# 28Pins_Schematic.net
KiCad netlist of a schematic drawn in Altium Designer
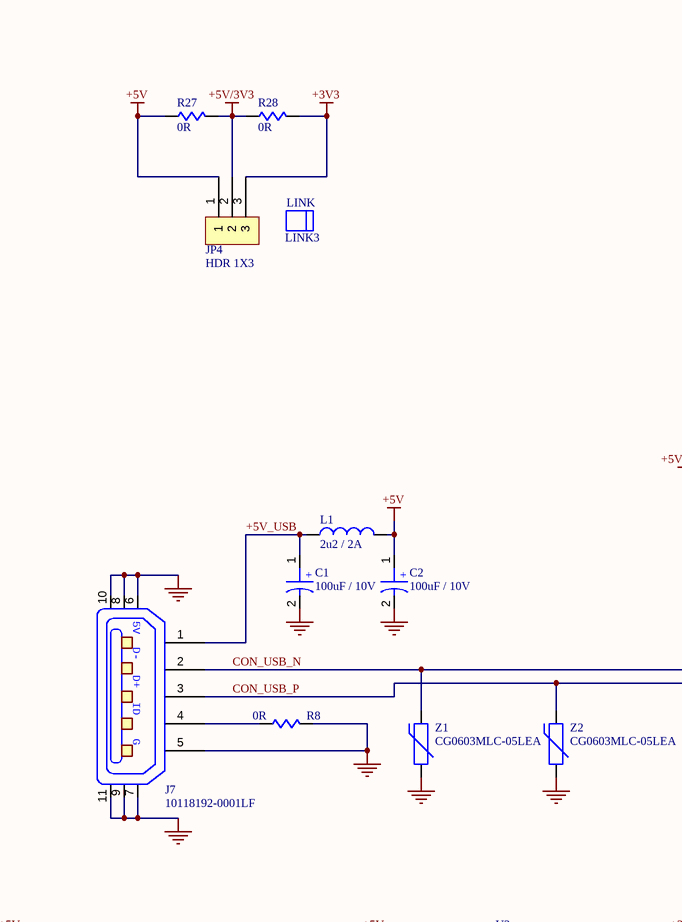
[diagram p0: 28Pins_Schematic.SchDoc, top left]
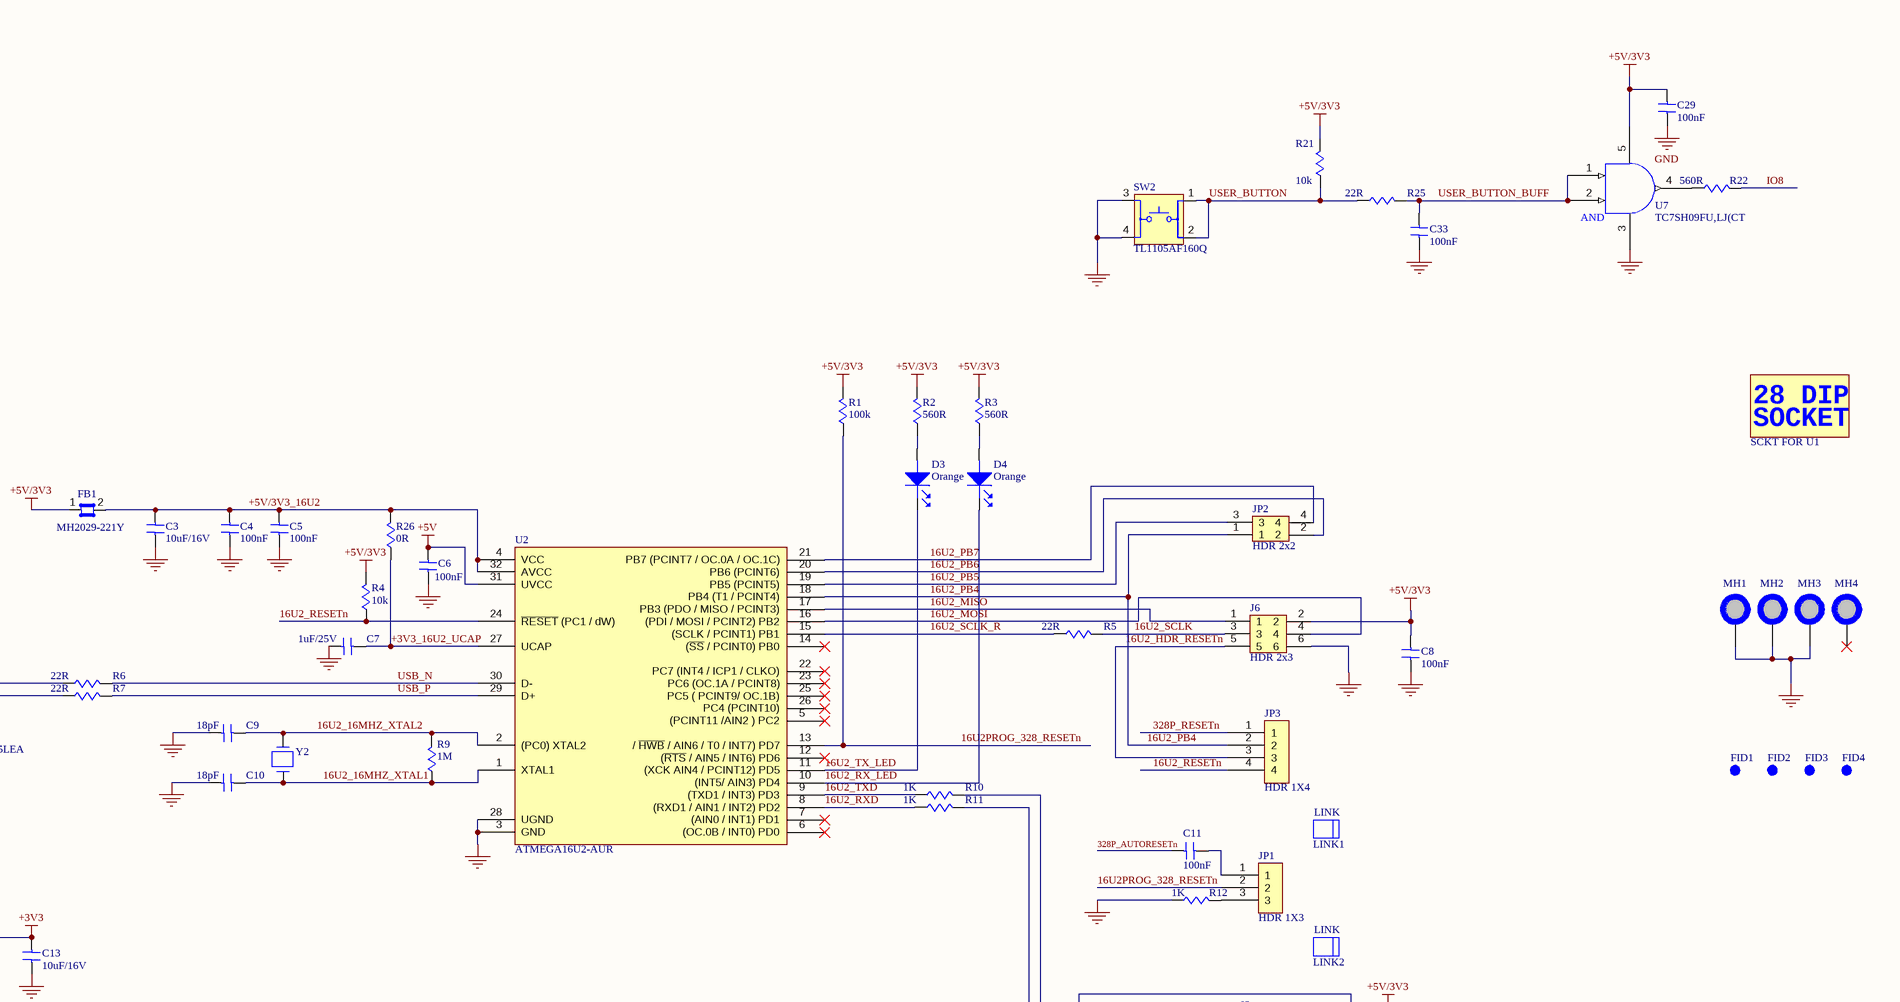
[diagram p1: 28Pins_Schematic.SchDoc, top right]
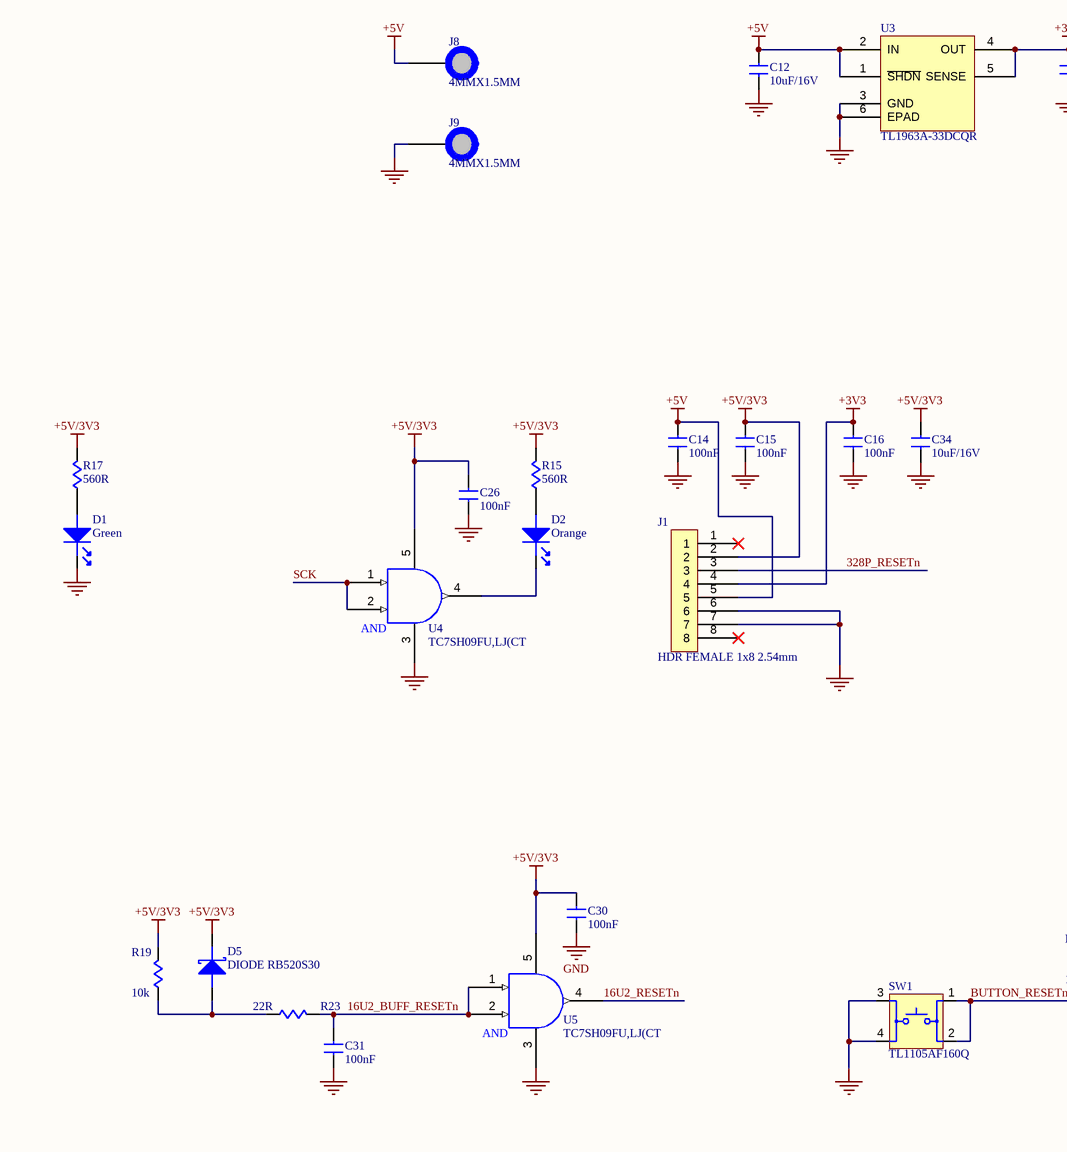
[diagram p2: 28Pins_Schematic.SchDoc, bottom left]
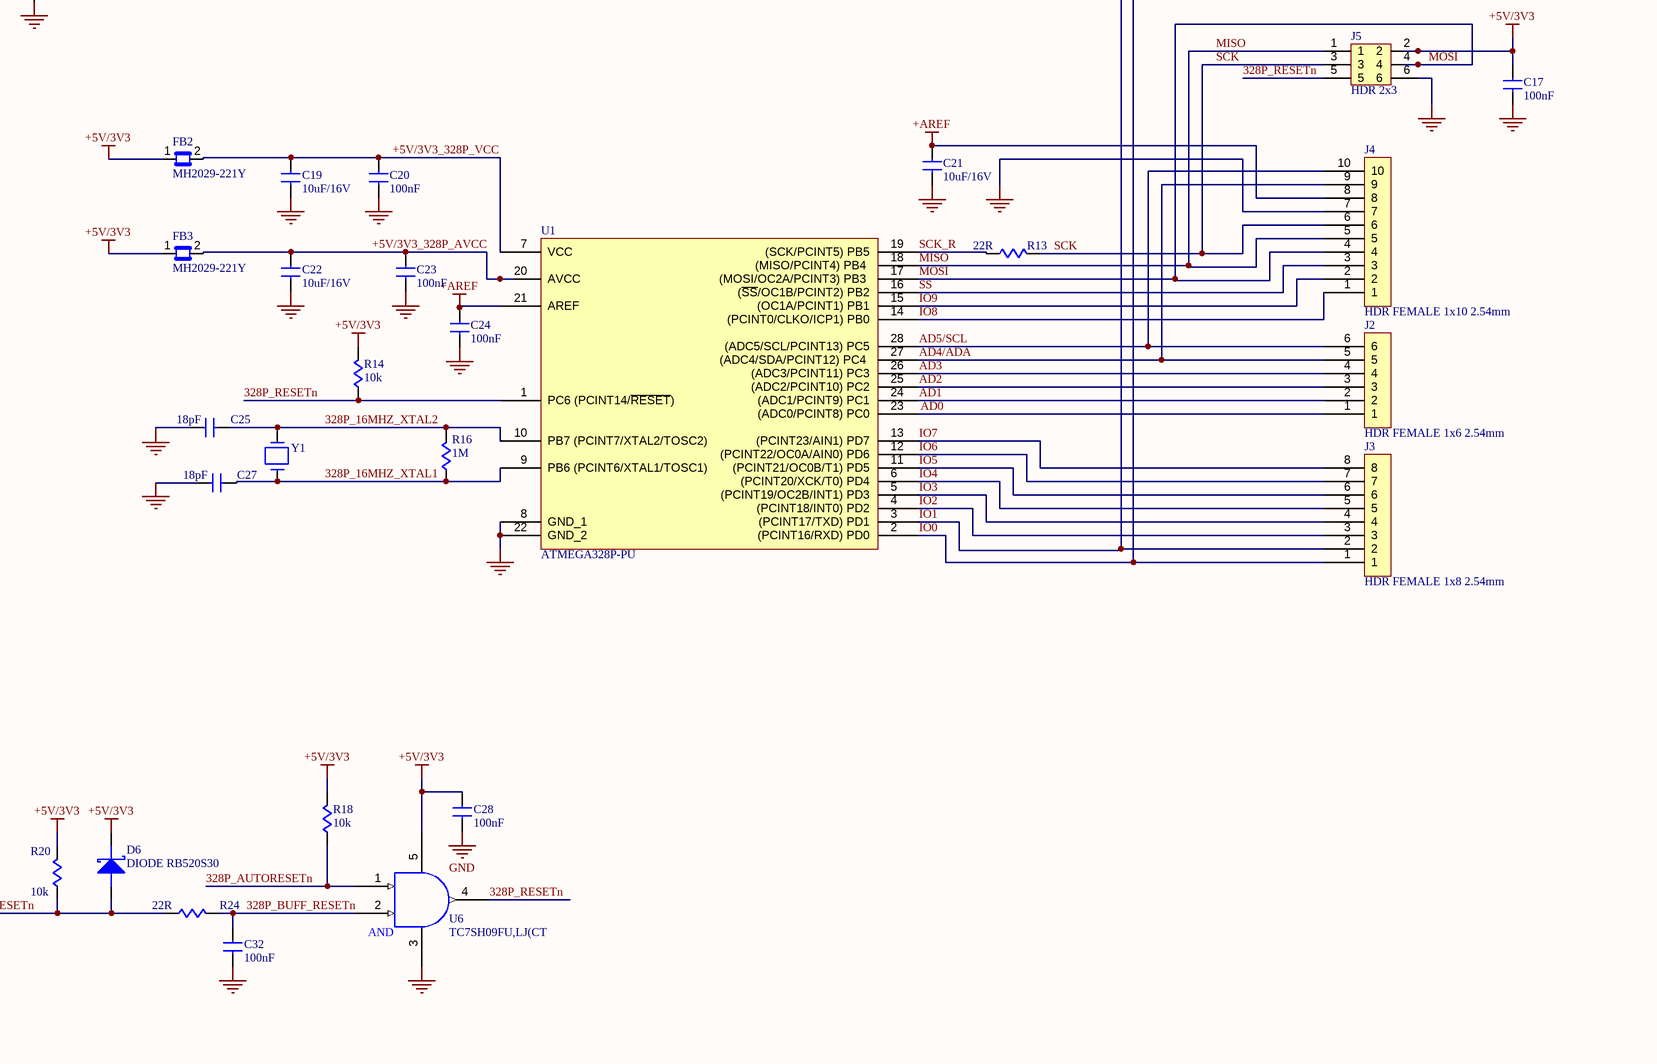
[diagram p3: 28Pins_Schematic.SchDoc, bottom right]

(export (version "E")
  (design (tool "Eeschema 10.0.6"))
  (components
    (comp (ref "C1")
      (value "100uF / 10V")
      (footprint "C_ALU_C_SIZE")
      (description "CAP ALUM 100UF 20% 10V SMD")
      (fields
        (field (name "MANUFACTURER") "Panasonic")
        (field (name "MANUFACTURER PART NUMBER") "EEE-1AA101WAR")
      )
      (libsource (lib "28Pins_Project") (part "EEE-1AA101WAR"))
    )
    (comp (ref "C2")
      (value "100uF / 10V")
      (footprint "C_ALU_C_SIZE")
      (description "CAP ALUM 100UF 20% 10V SMD")
      (fields
        (field (name "MANUFACTURER") "Panasonic")
        (field (name "MANUFACTURER PART NUMBER") "EEE-1AA101WAR")
      )
      (libsource (lib "28Pins_Project") (part "EEE-1AA101WAR"))
    )
    (comp (ref "C3")
      (value "10uF/16V")
      (footprint "C0805")
      (description "CAP CER 10UF 16V X5R 0805")
      (fields
        (field (name "MANUFACTURER") "Murata")
        (field (name "MANUFACTURER PART NUMBER") "GRM21BR61C106KE15L")
      )
      (libsource (lib "28Pins_Project") (part "GRM21BR61C106KE15L"))
    )
    (comp (ref "C4")
      (value "100nF")
      (footprint "C0805")
      (fields
        (field (name "MANUFACTURER") "Kyocera AVX")
        (field (name "MANUFACTURER PART NUMBER") "08055C104K4T4A")
        (field (name "TOLERANCE") "10%")
      )
      (libsource (lib "28Pins_Project") (part "08055C104K4T4A"))
    )
    (comp (ref "C5")
      (value "100nF")
      (footprint "C0805")
      (fields
        (field (name "MANUFACTURER") "Kyocera AVX")
        (field (name "MANUFACTURER PART NUMBER") "08055C104K4T4A")
        (field (name "TOLERANCE") "10%")
      )
      (libsource (lib "28Pins_Project") (part "08055C104K4T4A"))
    )
    (comp (ref "C6")
      (value "100nF")
      (footprint "C0805")
      (fields
        (field (name "MANUFACTURER") "Kyocera AVX")
        (field (name "MANUFACTURER PART NUMBER") "08055C104K4T4A")
        (field (name "TOLERANCE") "10%")
      )
      (libsource (lib "28Pins_Project") (part "08055C104K4T4A"))
    )
    (comp (ref "C7")
      (value "1uF/25V")
      (footprint "C0805")
      (fields
        (field (name "MANUFACTURER") "TDK")
        (field (name "MANUFACTURER PART NUMBER") "C2012X5R1E105K125AA")
        (field (name "TOLERANCE") "10%")
      )
      (libsource (lib "28Pins_Project") (part "C2012X5R1E105K125AA"))
    )
    (comp (ref "C8")
      (value "100nF")
      (footprint "C0805")
      (fields
        (field (name "MANUFACTURER") "Kyocera AVX")
        (field (name "MANUFACTURER PART NUMBER") "08055C104K4T4A")
        (field (name "TOLERANCE") "10%")
      )
      (libsource (lib "28Pins_Project") (part "08055C104K4T4A"))
    )
    (comp (ref "C9")
      (value "18pF")
      (footprint "C0805")
      (description "CAP CER 18pF")
      (fields
        (field (name "MANUFACTURER") "Murata")
        (field (name "MANUFACTURER PART NUMBER") "GJM1551C1HR56BB01D")
      )
      (libsource (lib "28Pins_Project") (part "GJM1551C1HR56BB01D"))
    )
    (comp (ref "C10")
      (value "18pF")
      (footprint "C0805")
      (description "CAP CER 18pF")
      (fields
        (field (name "MANUFACTURER") "Murata")
        (field (name "MANUFACTURER PART NUMBER") "GJM1551C1HR56BB01D")
      )
      (libsource (lib "28Pins_Project") (part "GJM1551C1HR56BB01D"))
    )
    (comp (ref "C11")
      (value "100nF")
      (footprint "C0805")
      (fields
        (field (name "MANUFACTURER") "Kyocera AVX")
        (field (name "MANUFACTURER PART NUMBER") "08055C104K4T4A")
        (field (name "TOLERANCE") "10%")
      )
      (libsource (lib "28Pins_Project") (part "08055C104K4T4A"))
    )
    (comp (ref "C12")
      (value "10uF/16V")
      (footprint "C0805")
      (description "CAP CER 10UF 16V X5R 0805")
      (fields
        (field (name "MANUFACTURER") "Murata")
        (field (name "MANUFACTURER PART NUMBER") "GRM21BR61C106KE15L")
      )
      (libsource (lib "28Pins_Project") (part "GRM21BR61C106KE15L"))
    )
    (comp (ref "C13")
      (value "10uF/16V")
      (footprint "C0805")
      (description "CAP CER 10UF 16V X5R 0805")
      (fields
        (field (name "MANUFACTURER") "Murata")
        (field (name "MANUFACTURER PART NUMBER") "GRM21BR61C106KE15L")
      )
      (libsource (lib "28Pins_Project") (part "GRM21BR61C106KE15L"))
    )
    (comp (ref "C14")
      (value "100nF")
      (footprint "C0805")
      (fields
        (field (name "MANUFACTURER") "Kyocera AVX")
        (field (name "MANUFACTURER PART NUMBER") "08055C104K4T4A")
        (field (name "TOLERANCE") "10%")
      )
      (libsource (lib "28Pins_Project") (part "08055C104K4T4A"))
    )
    (comp (ref "C15")
      (value "100nF")
      (footprint "C0805")
      (fields
        (field (name "MANUFACTURER") "Kyocera AVX")
        (field (name "MANUFACTURER PART NUMBER") "08055C104K4T4A")
        (field (name "TOLERANCE") "10%")
      )
      (libsource (lib "28Pins_Project") (part "08055C104K4T4A"))
    )
    (comp (ref "C16")
      (value "100nF")
      (footprint "C0805")
      (fields
        (field (name "MANUFACTURER") "Kyocera AVX")
        (field (name "MANUFACTURER PART NUMBER") "08055C104K4T4A")
        (field (name "TOLERANCE") "10%")
      )
      (libsource (lib "28Pins_Project") (part "08055C104K4T4A"))
    )
    (comp (ref "C17")
      (value "100nF")
      (footprint "C0805")
      (fields
        (field (name "MANUFACTURER") "Kyocera AVX")
        (field (name "MANUFACTURER PART NUMBER") "08055C104K4T4A")
        (field (name "TOLERANCE") "10%")
      )
      (libsource (lib "28Pins_Project") (part "08055C104K4T4A"))
    )
    (comp (ref "C19")
      (value "10uF/16V")
      (footprint "C0805")
      (description "CAP CER 10UF 16V X5R 0805")
      (fields
        (field (name "MANUFACTURER") "Murata")
        (field (name "MANUFACTURER PART NUMBER") "GRM21BR61C106KE15L")
      )
      (libsource (lib "28Pins_Project") (part "GRM21BR61C106KE15L"))
    )
    (comp (ref "C20")
      (value "100nF")
      (footprint "C0805")
      (fields
        (field (name "MANUFACTURER") "Kyocera AVX")
        (field (name "MANUFACTURER PART NUMBER") "08055C104K4T4A")
        (field (name "TOLERANCE") "10%")
      )
      (libsource (lib "28Pins_Project") (part "08055C104K4T4A"))
    )
    (comp (ref "C21")
      (value "10uF/16V")
      (footprint "C0805")
      (description "CAP CER 10UF 16V X5R 0805")
      (fields
        (field (name "MANUFACTURER") "Murata")
        (field (name "MANUFACTURER PART NUMBER") "GRM21BR61C106KE15L")
      )
      (libsource (lib "28Pins_Project") (part "GRM21BR61C106KE15L"))
    )
    (comp (ref "C22")
      (value "10uF/16V")
      (footprint "C0805")
      (description "CAP CER 10UF 16V X5R 0805")
      (fields
        (field (name "MANUFACTURER") "Murata")
        (field (name "MANUFACTURER PART NUMBER") "GRM21BR61C106KE15L")
      )
      (libsource (lib "28Pins_Project") (part "GRM21BR61C106KE15L"))
    )
    (comp (ref "C23")
      (value "100nF")
      (footprint "C0805")
      (fields
        (field (name "MANUFACTURER") "Kyocera AVX")
        (field (name "MANUFACTURER PART NUMBER") "08055C104K4T4A")
        (field (name "TOLERANCE") "10%")
      )
      (libsource (lib "28Pins_Project") (part "08055C104K4T4A"))
    )
    (comp (ref "C24")
      (value "100nF")
      (footprint "C0805")
      (fields
        (field (name "MANUFACTURER") "Kyocera AVX")
        (field (name "MANUFACTURER PART NUMBER") "08055C104K4T4A")
        (field (name "TOLERANCE") "10%")
      )
      (libsource (lib "28Pins_Project") (part "08055C104K4T4A"))
    )
    (comp (ref "C25")
      (value "18pF")
      (footprint "C0805")
      (description "CAP CER 18pF")
      (fields
        (field (name "MANUFACTURER") "Murata")
        (field (name "MANUFACTURER PART NUMBER") "GJM1551C1HR56BB01D")
      )
      (libsource (lib "28Pins_Project") (part "GJM1551C1HR56BB01D"))
    )
    (comp (ref "C26")
      (value "100nF")
      (footprint "C0805")
      (fields
        (field (name "MANUFACTURER") "Kyocera AVX")
        (field (name "MANUFACTURER PART NUMBER") "08055C104K4T4A")
        (field (name "TOLERANCE") "10%")
      )
      (libsource (lib "28Pins_Project") (part "08055C104K4T4A"))
    )
    (comp (ref "C27")
      (value "18pF")
      (footprint "C0805")
      (description "CAP CER 18pF")
      (fields
        (field (name "MANUFACTURER") "Murata")
        (field (name "MANUFACTURER PART NUMBER") "GJM1551C1HR56BB01D")
      )
      (libsource (lib "28Pins_Project") (part "GJM1551C1HR56BB01D"))
    )
    (comp (ref "C28")
      (value "100nF")
      (footprint "C0805")
      (fields
        (field (name "MANUFACTURER") "Kyocera AVX")
        (field (name "MANUFACTURER PART NUMBER") "08055C104K4T4A")
        (field (name "TOLERANCE") "10%")
      )
      (libsource (lib "28Pins_Project") (part "08055C104K4T4A"))
    )
    (comp (ref "C29")
      (value "100nF")
      (footprint "C0805")
      (fields
        (field (name "MANUFACTURER") "Kyocera AVX")
        (field (name "MANUFACTURER PART NUMBER") "08055C104K4T4A")
        (field (name "TOLERANCE") "10%")
      )
      (libsource (lib "28Pins_Project") (part "08055C104K4T4A"))
    )
    (comp (ref "C30")
      (value "100nF")
      (footprint "C0805")
      (fields
        (field (name "MANUFACTURER") "Kyocera AVX")
        (field (name "MANUFACTURER PART NUMBER") "08055C104K4T4A")
        (field (name "TOLERANCE") "10%")
      )
      (libsource (lib "28Pins_Project") (part "08055C104K4T4A"))
    )
    (comp (ref "C31")
      (value "100nF")
      (footprint "C0805")
      (fields
        (field (name "MANUFACTURER") "Kyocera AVX")
        (field (name "MANUFACTURER PART NUMBER") "08055C104K4T4A")
        (field (name "TOLERANCE") "10%")
      )
      (libsource (lib "28Pins_Project") (part "08055C104K4T4A"))
    )
    (comp (ref "C32")
      (value "100nF")
      (footprint "C0805")
      (fields
        (field (name "MANUFACTURER") "Kyocera AVX")
        (field (name "MANUFACTURER PART NUMBER") "08055C104K4T4A")
        (field (name "TOLERANCE") "10%")
      )
      (libsource (lib "28Pins_Project") (part "08055C104K4T4A"))
    )
    (comp (ref "C33")
      (value "100nF")
      (footprint "C0805")
      (fields
        (field (name "MANUFACTURER") "Kyocera AVX")
        (field (name "MANUFACTURER PART NUMBER") "08055C104K4T4A")
        (field (name "TOLERANCE") "10%")
      )
      (libsource (lib "28Pins_Project") (part "08055C104K4T4A"))
    )
    (comp (ref "C34")
      (value "10uF/16V")
      (footprint "C0805")
      (description "CAP CER 10UF 16V X5R 0805")
      (fields
        (field (name "MANUFACTURER") "Murata")
        (field (name "MANUFACTURER PART NUMBER") "GRM21BR61C106KE15L")
      )
      (libsource (lib "28Pins_Project") (part "GRM21BR61C106KE15L"))
    )
    (comp (ref "D1")
      (value "Green")
      (footprint "LED_0603")
      (description "LED Uni-Color Green 572nm Automotive 2-Pin Chip 0603(1608Metric) T/R")
      (fields
        (field (name "MANUFACTURER") "Osram Opto")
        (field (name "MANUFACTURER PART NUMBER") "LGL29K-F2J1-24-Z")
      )
      (libsource (lib "28Pins_Project") (part "LGL29K-F2J1-24-Z"))
    )
    (comp (ref "D2")
      (value "Orange")
      (footprint "LED_0603")
      (description "OSRAM - LO L29K-H2K1-24-Z - SMARTLED 0603 ORANGE 55AC2374")
      (fields
        (field (name "MANUFACTURER") "Osram Opto")
        (field (name "MANUFACTURER PART NUMBER") "LOL29K-H2K1-24-Z")
      )
      (libsource (lib "28Pins_Project") (part "LOL29K-H2K1-24-Z"))
    )
    (comp (ref "D3")
      (value "Orange")
      (footprint "LED_0603")
      (description "OSRAM - LO L29K-H2K1-24-Z - SMARTLED 0603 ORANGE 55AC2374")
      (fields
        (field (name "MANUFACTURER") "Osram Opto")
        (field (name "MANUFACTURER PART NUMBER") "LOL29K-H2K1-24-Z")
      )
      (libsource (lib "28Pins_Project") (part "LOL29K-H2K1-24-Z"))
    )
    (comp (ref "D4")
      (value "Orange")
      (footprint "LED_0603")
      (description "OSRAM - LO L29K-H2K1-24-Z - SMARTLED 0603 ORANGE 55AC2374")
      (fields
        (field (name "MANUFACTURER") "Osram Opto")
        (field (name "MANUFACTURER PART NUMBER") "LOL29K-H2K1-24-Z")
      )
      (libsource (lib "28Pins_Project") (part "LOL29K-H2K1-24-Z"))
    )
    (comp (ref "D5")
      (value "DIODE RB520S30")
      (footprint "SOD523")
      (description "DIODE, SCHOTTKY, 200mA, 30V, SOD-523F FAIRCHILD SEMICONDUCTOR RB520S30")
      (fields
        (field (name "MANUFACTURER") "ON Semiconductor / Fairchild")
        (field (name "MANUFACTURER PART NUMBER") "RB520S30")
      )
      (libsource (lib "28Pins_Project") (part "RB520S30"))
    )
    (comp (ref "D6")
      (value "DIODE RB520S30")
      (footprint "SOD523")
      (description "DIODE, SCHOTTKY, 200mA, 30V, SOD-523F FAIRCHILD SEMICONDUCTOR RB520S30")
      (fields
        (field (name "MANUFACTURER") "ON Semiconductor / Fairchild")
        (field (name "MANUFACTURER PART NUMBER") "RB520S30")
      )
      (libsource (lib "28Pins_Project") (part "RB520S30"))
    )
    (comp (ref "FB1")
      (value "MH2029-221Y")
      (footprint "FB0805")
      (description "BEAD FERRITE 220 OHM 2.0A 0805")
      (fields (field (name "MANUFACTURER") "Bourns") (field (name "TOLERANCE") "25%"))
      (libsource (lib "28Pins_Project") (part "MH2029-221Y"))
    )
    (comp (ref "FB2")
      (value "MH2029-221Y")
      (footprint "FB0805")
      (description "BEAD FERRITE 220 OHM 2.0A 0805")
      (fields (field (name "MANUFACTURER") "Bourns") (field (name "TOLERANCE") "25%"))
      (libsource (lib "28Pins_Project") (part "MH2029-221Y"))
    )
    (comp (ref "FB3")
      (value "MH2029-221Y")
      (footprint "FB0805")
      (description "BEAD FERRITE 220 OHM 2.0A 0805")
      (fields (field (name "MANUFACTURER") "Bourns") (field (name "TOLERANCE") "25%"))
      (libsource (lib "28Pins_Project") (part "MH2029-221Y"))
    )
    (comp (ref "FID1")
      (value "Fiducial 40mil Diameter 120mil solder mask")
      (footprint "FID_40X120D")
      (libsource (lib "28Pins_Project") (part "FID_1MMC"))
    )
    (comp (ref "FID2")
      (value "Fiducial 40mil Diameter 120mil solder mask")
      (footprint "FID_40X120D")
      (libsource (lib "28Pins_Project") (part "FID_1MMC"))
    )
    (comp (ref "FID3")
      (value "Fiducial 40mil Diameter 120mil solder mask")
      (footprint "FID_40X120D")
      (libsource (lib "28Pins_Project") (part "FID_1MMC"))
    )
    (comp (ref "FID4")
      (value "Fiducial 40mil Diameter 120mil solder mask")
      (footprint "FID_40X120D")
      (libsource (lib "28Pins_Project") (part "FID_1MMC"))
    )
    (comp (ref "J1")
      (value "HDR FEMALE 1x8 2.54mm")
      (footprint "HDR_FEMALE_1x8_2.54mm")
      (description "CONN HEADER 8POS 0.1\" PITCH")
      (fields (field (name "MANUFACTURER") "Harwin") (field (name "MANUFACTURER PART NUMBER") "M20-7820842"))
      (libsource (lib "28Pins_Project") (part "M20-7820842"))
    )
    (comp (ref "J2")
      (value "HDR FEMALE 1x6 2.54mm")
      (footprint "HDR_FEMALE_1x6_2.54mm - duplicate")
      (description "CONN HEADER 6POS 0.1\" PITCH")
      (fields (field (name "MANUFACTURER") "Harwin") (field (name "MANUFACTURER PART NUMBER") "M20-7820646"))
      (libsource (lib "28Pins_Project") (part "M20-7820646"))
    )
    (comp (ref "J3")
      (value "HDR FEMALE 1x8 2.54mm")
      (footprint "HDR_FEMALE_1x8_2.54mm")
      (description "CONN HEADER 8POS 0.1\" PITCH")
      (fields (field (name "MANUFACTURER") "Harwin") (field (name "MANUFACTURER PART NUMBER") "M20-7820842"))
      (libsource (lib "") (part "M20-7820842_1"))
    )
    (comp (ref "J4")
      (value "HDR FEMALE 1x10 2.54mm")
      (footprint "HDR_FEMALE_1x10_2.54mm")
      (description "CONN HEADER 10POS 0.1\" PITCH HARWIN - M20-7821046")
      (fields (field (name "MANUFACTURER") "Harwin") (field (name "MANUFACTURER PART NUMBER") "M20-7821046"))
      (libsource (lib "28Pins_Project") (part "M20-7821046"))
    )
    (comp (ref "J5")
      (value "HDR 2x3")
      (footprint "HDR2X3_2.54MM")
      (description "AMPHENOL FCI   68602-206HLF   BOARD TO BOARD, HEADER, 6 POSITION, 2ROW")
      (fields
        (field (name "MANUFACTURER") "Amphenol ICC / FCI")
        (field (name "MANUFACTURER PART NUMBER") "68602-206HLF")
      )
      (libsource (lib "28Pins_Project") (part "68602-206HLF"))
    )
    (comp (ref "J6")
      (value "HDR 2x3")
      (footprint "HDR2X3_2.54MM")
      (description "AMPHENOL FCI   68602-206HLF   BOARD TO BOARD, HEADER, 6 POSITION, 2ROW")
      (fields
        (field (name "MANUFACTURER") "Amphenol ICC / FCI")
        (field (name "MANUFACTURER PART NUMBER") "68602-206HLF")
      )
      (libsource (lib "28Pins_Project") (part "68602-206HLF"))
    )
    (comp (ref "J7")
      (value "10118192-0001LF")
      (footprint "10118192")
      (description "CONN USB MICRO B RECPT SMT R/A")
      (fields (field (name "MANUFACTURER") "Amphenol ICC / FCI"))
      (libsource (lib "28Pins_Project") (part "10118192-0001LF"))
    )
    (comp (ref "J8")
      (value "4MMX1.5MM")
      (footprint "PAD_WITH_HOLE_4MMX1.5MM")
      (description "Pad with a hole 4mm x 1.5mm")
      (libsource (lib "28Pins_Project") (part "PAD_WITH_HOLE"))
    )
    (comp (ref "J9")
      (value "4MMX1.5MM")
      (footprint "PAD_WITH_HOLE_4MMX1.5MM")
      (description "Pad with a hole 4mm x 1.5mm")
      (libsource (lib "28Pins_Project") (part "PAD_WITH_HOLE"))
    )
    (comp (ref "JP1")
      (value "HDR 1X3")
      (footprint "HDR1X3_2.54MM")
      (description "CONN HEADER 3POS 0.1\" PITCH AMPHENOL ICC - 68000-103HLF, FCI BergStik II 68000 Series")
      (fields
        (field (name "MANUFACTURER") "Amphenol ICC")
        (field (name "MANUFACTURER PART NUMBER") "68000-103HLF")
      )
      (libsource (lib "") (part "68000-103HLF_1"))
    )
    (comp (ref "JP2")
      (value "HDR 2x2")
      (footprint "HDR2X2_2.54MM")
      (fields
        (field (name "MANUFACTURER") "AMPHENOL ICC (FCI)")
        (field (name "MANUFACTURER PART NUMBER") "77313-124-04LF")
      )
      (libsource (lib "28Pins_Project") (part "77313-124-04LF"))
    )
    (comp (ref "JP3")
      (value "HDR 1X4")
      (footprint "HDR_1x4_2.54mm")
      (description "CONN HEADER 4 POS 2.54mm Solder ST Thru-Hole Bag")
      (fields (field (name "MANUFACTURER") "ICC") (field (name "MANUFACTURER PART NUMBER") "68001-204HLF"))
      (libsource (lib "28Pins_Project") (part "68001-204HLF"))
    )
    (comp (ref "JP4")
      (value "HDR 1X3")
      (footprint "HDR1X3_2.54MM")
      (description "CONN HEADER 3POS 0.1\" PITCH AMPHENOL ICC - 68000-103HLF, FCI BergStik II 68000 Series")
      (fields
        (field (name "MANUFACTURER") "Amphenol ICC")
        (field (name "MANUFACTURER PART NUMBER") "68000-103HLF")
      )
      (libsource (lib "28Pins_Project") (part "68000-103HLF"))
    )
    (comp (ref "L1")
      (value "2u2 / 2A")
      (footprint "C1210_IND")
      (description "INDUCTOR  L1210R2R2MDWIT KEMET")
      (fields
        (field (name "MANUFACTURER") "KEMET")
        (field (name "MANUFACTURER PART NUMBER") "L1210R2R2MDWIT")
      )
      (libsource (lib "28Pins_Project") (part "L1210R2R2MDWIT"))
    )
    (comp (ref "LINK1")
      (value "LINK")
      (description "CONN JUMPER SHORTING .100\" GOLD")
      (fields
        (field (name "MANUFACTURER") "Sullins")
        (field (name "MANUFACTURER PART NUMBER") "QPC02SXGN-RC")
      )
      (libsource (lib "28Pins_Project") (part "QPC02SXGN-RC"))
    )
    (comp (ref "LINK2")
      (value "LINK")
      (description "CONN JUMPER SHORTING .100\" GOLD")
      (fields
        (field (name "MANUFACTURER") "Sullins")
        (field (name "MANUFACTURER PART NUMBER") "QPC02SXGN-RC")
      )
      (libsource (lib "28Pins_Project") (part "QPC02SXGN-RC"))
    )
    (comp (ref "LINK3")
      (value "LINK")
      (description "CONN JUMPER SHORTING .100\" GOLD")
      (fields
        (field (name "MANUFACTURER") "Sullins")
        (field (name "MANUFACTURER PART NUMBER") "QPC02SXGN-RC")
      )
      (libsource (lib "28Pins_Project") (part "QPC02SXGN-RC"))
    )
    (comp (ref "MH1")
      (value "MH_7.4MMC_3.2MMD")
      (footprint "MH_7.4MMD_3.2MMD")
      (description "Mounting hole 7.4mm diameter, 3.2mm drill")
      (libsource (lib "28Pins_Project") (part "MH_7.4MMC_3.2"))
    )
    (comp (ref "MH2")
      (value "MH_7.4MMC_3.2MMD")
      (footprint "MH_7.4MMD_3.2MMD")
      (description "Mounting hole 7.4mm diameter, 3.2mm drill")
      (libsource (lib "28Pins_Project") (part "MH_7.4MMC_3.2"))
    )
    (comp (ref "MH3")
      (value "MH_7.4MMC_3.2MMD")
      (footprint "MH_7.4MMD_3.2MMD")
      (description "Mounting hole 7.4mm diameter, 3.2mm drill")
      (libsource (lib "28Pins_Project") (part "MH_7.4MMC_3.2"))
    )
    (comp (ref "MH4")
      (value "MH_7.4MMNC_3.2MMD")
      (footprint "MH_7.2MMD_4.2MMD_NON_COPPER_NPTH")
      (description "Hole 7.4mm diamter (non copper) 3.2 mm dril NPTH")
      (libsource (lib "28Pins_Project") (part "MH_7.4MMNC_3.2MMD"))
    )
    (comp (ref "R1")
      (value "100k")
      (footprint "R0805")
      (description "Res Thick Film 0805 100K Ohm 1% 1/8W ±100ppm/°C Molded SMD Paper T/R")
      (fields
        (field (name "MANUFACTURER") "Yageo")
        (field (name "MANUFACTURER PART NUMBER") "RC0805FR-07100KL")
      )
      (libsource (lib "28Pins_Project") (part "RC0805FR-07100KL"))
    )
    (comp (ref "R2")
      (value "560R")
      (footprint "R0805")
      (description "Surface Mount Thick Film Resistor, RC Series, 560 ohm, 125 mW, - 1%, 150 V, 0805 [2012 Metric]")
      (fields
        (field (name "MANUFACTURER") "Yageo")
        (field (name "MANUFACTURER PART NUMBER") "RC0805FR-07560RL")
      )
      (libsource (lib "28Pins_Project") (part "RC0805FR-07560RL"))
    )
    (comp (ref "R3")
      (value "560R")
      (footprint "R0805")
      (description "Surface Mount Thick Film Resistor, RC Series, 560 ohm, 125 mW, - 1%, 150 V, 0805 [2012 Metric]")
      (fields
        (field (name "MANUFACTURER") "Yageo")
        (field (name "MANUFACTURER PART NUMBER") "RC0805FR-07560RL")
      )
      (libsource (lib "28Pins_Project") (part "RC0805FR-07560RL"))
    )
    (comp (ref "R4")
      (value "10k")
      (footprint "R0805")
      (description "RES SMD 10K OHM 1% 1/8W 0805")
      (fields
        (field (name "MANUFACTURER") "Yageo")
        (field (name "MANUFACTURER PART NUMBER") "RC0805FR-0710KL")
      )
      (libsource (lib "28Pins_Project") (part "RC0805FR-0710KL"))
    )
    (comp (ref "R5")
      (value "22R")
      (footprint "R0805")
      (description "RES SMD 22 OHM 1% 1/8W 0805")
      (fields
        (field (name "MANUFACTURER") "Yageo")
        (field (name "MANUFACTURER PART NUMBER") "RC0805FR-0722RL")
      )
      (libsource (lib "28Pins_Project") (part "RC0805FR-0722RL"))
    )
    (comp (ref "R6")
      (value "22R")
      (footprint "R0805")
      (description "RES SMD 22 OHM 1% 1/8W 0805")
      (fields
        (field (name "MANUFACTURER") "Yageo")
        (field (name "MANUFACTURER PART NUMBER") "RC0805FR-0722RL")
      )
      (libsource (lib "28Pins_Project") (part "RC0805FR-0722RL"))
    )
    (comp (ref "R7")
      (value "22R")
      (footprint "R0805")
      (description "RES SMD 22 OHM 1% 1/8W 0805")
      (fields
        (field (name "MANUFACTURER") "Yageo")
        (field (name "MANUFACTURER PART NUMBER") "RC0805FR-0722RL")
      )
      (libsource (lib "28Pins_Project") (part "RC0805FR-0722RL"))
    )
    (comp (ref "R8")
      (value "0R")
      (footprint "R0805")
      (description "Res Anti-Sulfured Jumper Thick Film 0805 0 Ohm 1/8W Molded Paper T/R")
      (fields
        (field (name "MANUFACTURER") "Bourns")
        (field (name "MANUFACTURER PART NUMBER") "CR0805AJ/-000EAS")
      )
      (libsource (lib "28Pins_Project") (part "CR0805AJ/-000EAS"))
    )
    (comp (ref "R9")
      (value "1M")
      (footprint "R0805")
      (description "RES SMD 1M OHM 1% 1/8W 0805")
      (fields
        (field (name "MANUFACTURER") "Yageo")
        (field (name "MANUFACTURER PART NUMBER") "RC0805FR-071ML")
      )
      (libsource (lib "28Pins_Project") (part "RC0805FR-071ML"))
    )
    (comp (ref "R10")
      (value "1K")
      (footprint "R0805")
      (description "RES SMD 1K OHM 1% 1/8W 0805")
      (fields
        (field (name "MANUFACTURER") "Yageo")
        (field (name "MANUFACTURER PART NUMBER") "RC0805FR-071KL")
      )
      (libsource (lib "28Pins_Project") (part "RC0805FR-071KL"))
    )
    (comp (ref "R11")
      (value "1K")
      (footprint "R0805")
      (description "RES SMD 1K OHM 1% 1/8W 0805")
      (fields
        (field (name "MANUFACTURER") "Yageo")
        (field (name "MANUFACTURER PART NUMBER") "RC0805FR-071KL")
      )
      (libsource (lib "28Pins_Project") (part "RC0805FR-071KL"))
    )
    (comp (ref "R12")
      (value "1K")
      (footprint "R0805")
      (description "RES SMD 1K OHM 1% 1/8W 0805")
      (fields
        (field (name "MANUFACTURER") "Yageo")
        (field (name "MANUFACTURER PART NUMBER") "RC0805FR-071KL")
      )
      (libsource (lib "28Pins_Project") (part "RC0805FR-071KL"))
    )
    (comp (ref "R13")
      (value "22R")
      (footprint "R0805")
      (description "RES SMD 22 OHM 1% 1/8W 0805")
      (fields
        (field (name "MANUFACTURER") "Yageo")
        (field (name "MANUFACTURER PART NUMBER") "RC0805FR-0722RL")
      )
      (libsource (lib "28Pins_Project") (part "RC0805FR-0722RL"))
    )
    (comp (ref "R14")
      (value "10k")
      (footprint "R0805")
      (description "RES SMD 10K OHM 1% 1/8W 0805")
      (fields
        (field (name "MANUFACTURER") "Yageo")
        (field (name "MANUFACTURER PART NUMBER") "RC0805FR-0710KL")
      )
      (libsource (lib "28Pins_Project") (part "RC0805FR-0710KL"))
    )
    (comp (ref "R15")
      (value "560R")
      (footprint "R0805")
      (description "Surface Mount Thick Film Resistor, RC Series, 560 ohm, 125 mW, - 1%, 150 V, 0805 [2012 Metric]")
      (fields
        (field (name "MANUFACTURER") "Yageo")
        (field (name "MANUFACTURER PART NUMBER") "RC0805FR-07560RL")
      )
      (libsource (lib "28Pins_Project") (part "RC0805FR-07560RL"))
    )
    (comp (ref "R16")
      (value "1M")
      (footprint "R0805")
      (description "RES SMD 1M OHM 1% 1/8W 0805")
      (fields
        (field (name "MANUFACTURER") "Yageo")
        (field (name "MANUFACTURER PART NUMBER") "RC0805FR-071ML")
      )
      (libsource (lib "28Pins_Project") (part "RC0805FR-071ML"))
    )
    (comp (ref "R17")
      (value "560R")
      (footprint "R0805")
      (description "Surface Mount Thick Film Resistor, RC Series, 560 ohm, 125 mW, - 1%, 150 V, 0805 [2012 Metric]")
      (fields
        (field (name "MANUFACTURER") "Yageo")
        (field (name "MANUFACTURER PART NUMBER") "RC0805FR-07560RL")
      )
      (libsource (lib "28Pins_Project") (part "RC0805FR-07560RL"))
    )
    (comp (ref "R18")
      (value "10k")
      (footprint "R0805")
      (description "RES SMD 10K OHM 1% 1/8W 0805")
      (fields
        (field (name "MANUFACTURER") "Yageo")
        (field (name "MANUFACTURER PART NUMBER") "RC0805FR-0710KL")
      )
      (libsource (lib "28Pins_Project") (part "RC0805FR-0710KL"))
    )
    (comp (ref "R19")
      (value "10k")
      (footprint "R0805")
      (description "RES SMD 10K OHM 1% 1/8W 0805")
      (fields
        (field (name "MANUFACTURER") "Yageo")
        (field (name "MANUFACTURER PART NUMBER") "RC0805FR-0710KL")
      )
      (libsource (lib "28Pins_Project") (part "RC0805FR-0710KL"))
    )
    (comp (ref "R20")
      (value "10k")
      (footprint "R0805")
      (description "RES SMD 10K OHM 1% 1/8W 0805")
      (fields
        (field (name "MANUFACTURER") "Yageo")
        (field (name "MANUFACTURER PART NUMBER") "RC0805FR-0710KL")
      )
      (libsource (lib "28Pins_Project") (part "RC0805FR-0710KL"))
    )
    (comp (ref "R21")
      (value "10k")
      (footprint "R0805")
      (description "RES SMD 10K OHM 1% 1/8W 0805")
      (fields
        (field (name "MANUFACTURER") "Yageo")
        (field (name "MANUFACTURER PART NUMBER") "RC0805FR-0710KL")
      )
      (libsource (lib "28Pins_Project") (part "RC0805FR-0710KL"))
    )
    (comp (ref "R22")
      (value "560R")
      (footprint "R0805")
      (description "Surface Mount Thick Film Resistor, RC Series, 560 ohm, 125 mW, - 1%, 150 V, 0805 [2012 Metric]")
      (fields
        (field (name "MANUFACTURER") "Yageo")
        (field (name "MANUFACTURER PART NUMBER") "RC0805FR-07560RL")
      )
      (libsource (lib "28Pins_Project") (part "RC0805FR-07560RL"))
    )
    (comp (ref "R23")
      (value "22R")
      (footprint "R0805")
      (description "RES SMD 22 OHM 1% 1/8W 0805")
      (fields
        (field (name "MANUFACTURER") "Yageo")
        (field (name "MANUFACTURER PART NUMBER") "RC0805FR-0722RL")
      )
      (libsource (lib "28Pins_Project") (part "RC0805FR-0722RL"))
    )
    (comp (ref "R24")
      (value "22R")
      (footprint "R0805")
      (description "RES SMD 22 OHM 1% 1/8W 0805")
      (fields
        (field (name "MANUFACTURER") "Yageo")
        (field (name "MANUFACTURER PART NUMBER") "RC0805FR-0722RL")
      )
      (libsource (lib "28Pins_Project") (part "RC0805FR-0722RL"))
    )
    (comp (ref "R25")
      (value "22R")
      (footprint "R0805")
      (description "RES SMD 22 OHM 1% 1/8W 0805")
      (fields
        (field (name "MANUFACTURER") "Yageo")
        (field (name "MANUFACTURER PART NUMBER") "RC0805FR-0722RL")
      )
      (libsource (lib "28Pins_Project") (part "RC0805FR-0722RL"))
    )
    (comp (ref "R26")
      (value "0R")
      (footprint "R0805")
      (description "Res Anti-Sulfured Jumper Thick Film 0805 0 Ohm 1/8W Molded Paper T/R")
      (fields
        (field (name "MANUFACTURER") "Bourns")
        (field (name "MANUFACTURER PART NUMBER") "CR0805AJ/-000EAS")
      )
      (libsource (lib "28Pins_Project") (part "CR0805AJ/-000EAS"))
    )
    (comp (ref "R27")
      (value "0R")
      (footprint "R0805")
      (description "Res Anti-Sulfured Jumper Thick Film 0805 0 Ohm 1/8W Molded Paper T/R")
      (fields
        (field (name "MANUFACTURER") "Bourns")
        (field (name "MANUFACTURER PART NUMBER") "CR0805AJ/-000EAS")
      )
      (libsource (lib "28Pins_Project") (part "CR0805AJ/-000EAS"))
    )
    (comp (ref "R28")
      (value "0R")
      (footprint "R0805")
      (description "Res Anti-Sulfured Jumper Thick Film 0805 0 Ohm 1/8W Molded Paper T/R")
      (fields
        (field (name "MANUFACTURER") "Bourns")
        (field (name "MANUFACTURER PART NUMBER") "CR0805AJ/-000EAS")
      )
      (libsource (lib "28Pins_Project") (part "CR0805AJ/-000EAS"))
    )
    (comp (ref "SCKT FOR U1")
      (value "28-DIP Socket")
      (footprint "28_DIP_7.62MM_SOCKET")
      (description "Conn DIP Socket SKT 28 POS 2.54mm Solder ST Thru-Hole")
      (fields (field (name "MANUFACTURER") "3M") (field (name "MANUFACTURER PART NUMBER") "4828-6004-CP"))
      (libsource (lib "28Pins_Project") (part "4828-6004-CP"))
    )
    (comp (ref "SW1")
      (value "TL1105AF160Q")
      (footprint "TL1105AF160Q")
      (description "Switch Tactile N.O. SPST Round Button PC Pins 0.05A 50VDC 1.57N Thru-Hole")
      (fields (field (name "MANUFACTURER") "E-Switch"))
      (libsource (lib "28Pins_Project") (part "TL1105AF160Q"))
    )
    (comp (ref "SW2")
      (value "TL1105AF160Q")
      (footprint "TL1105AF160Q")
      (description "Switch Tactile N.O. SPST Round Button PC Pins 0.05A 50VDC 1.57N Thru-Hole")
      (fields (field (name "MANUFACTURER") "E-Switch"))
      (libsource (lib "28Pins_Project") (part "TL1105AF160Q"))
    )
    (comp (ref "U1")
      (value "ATMEGA328P-PU")
      (footprint "DIP28_300mil")
      (description "IC MCU 8BIT 32KB FLASH 28DIP")
      (fields (field (name "MANUFACTURER") "Microchip / Atmel"))
      (libsource (lib "28Pins_Project") (part "ATMEGA328P-PU"))
    )
    (comp (ref "U2")
      (value "ATMEGA16U2-AUR")
      (footprint "TQFP32")
      (description "IC MCU 8BIT 16KB FLASH 32TQFP")
      (fields (field (name "MANUFACTURER") "Microchip / Atmel"))
      (libsource (lib "28Pins_Project") (part "ATMEGA16U2-AUR"))
    )
    (comp (ref "U3")
      (value "TL1963A-33DCQR")
      (footprint "DCQ (R-PDSO-G6)")
      (description "IC REG LINEAR 3.3V 1.5A SOT223-6")
      (fields (field (name "MANUFACTURER") "Texas Instruments"))
      (libsource (lib "28Pins_Project") (part "TL1963A-33DCQR"))
    )
    (comp (ref "U4")
      (value "TC7SH09FU,LJ(CT")
      (footprint "TC7SH09FU")
      (description "AND Gate 1-Element 2-IN CMOS 5-Pin SSOP")
      (fields (field (name "MANUFACTURER") "Toshiba"))
      (libsource (lib "28Pins_Project") (part "TC7SH09FU,LJ(CT"))
    )
    (comp (ref "U5")
      (value "TC7SH09FU,LJ(CT")
      (footprint "TC7SH09FU")
      (description "AND Gate 1-Element 2-IN CMOS 5-Pin SSOP")
      (fields (field (name "MANUFACTURER") "Toshiba"))
      (libsource (lib "28Pins_Project") (part "TC7SH09FU,LJ(CT"))
    )
    (comp (ref "U6")
      (value "TC7SH09FU,LJ(CT")
      (footprint "TC7SH09FU")
      (description "AND Gate 1-Element 2-IN CMOS 5-Pin SSOP")
      (fields (field (name "MANUFACTURER") "Toshiba"))
      (libsource (lib "28Pins_Project") (part "TC7SH09FU,LJ(CT"))
    )
    (comp (ref "U7")
      (value "TC7SH09FU,LJ(CT")
      (footprint "TC7SH09FU")
      (description "AND Gate 1-Element 2-IN CMOS 5-Pin SSOP")
      (fields (field (name "MANUFACTURER") "Toshiba"))
      (libsource (lib "28Pins_Project") (part "TC7SH09FU,LJ(CT"))
    )
    (comp (ref "Y1")
      (value "ABM7-16.000MHZ-4-T")
      (footprint "ABM7_v1_BIG")
      (description "CRYSTAL 16.0000 MHZ")
      (fields (field (name "MANUFACTURER") "Abracon"))
      (libsource (lib "28Pins_Project") (part "ABM7-16.000MHZ-4-T"))
    )
    (comp (ref "Y2")
      (value "ABM7-16.000MHZ-4-T")
      (footprint "ABM7_v1_BIG")
      (description "CRYSTAL 16.0000 MHZ")
      (fields (field (name "MANUFACTURER") "Abracon"))
      (libsource (lib "28Pins_Project") (part "ABM7-16.000MHZ-4-T"))
    )
    (comp (ref "Z1")
      (value "CG0603MLC-05LEA")
      (footprint "R0603")
      (description "CHIP GUARD")
      (fields (field (name "MANUFACTURER") "Bourns") (field (name "VOLTAGE") "5V"))
      (libsource (lib "28Pins_Project") (part "CG0603MLC-05LEA"))
    )
    (comp (ref "Z2")
      (value "CG0603MLC-05LEA")
      (footprint "R0603")
      (description "CHIP GUARD")
      (fields (field (name "MANUFACTURER") "Bourns") (field (name "VOLTAGE") "5V"))
      (libsource (lib "28Pins_Project") (part "CG0603MLC-05LEA"))
    )
  )
  (nets
    (net (code "1") (name "+3V3") (class "Default")
      (node (ref "C13") (pin "2") (pinfunction "2_2") (pintype "passive"))
      (node (ref "C16") (pin "2") (pinfunction "2_2") (pintype "passive"))
      (node (ref "J1") (pin "4") (pinfunction "4_4") (pintype "passive"))
      (node (ref "JP4") (pin "3") (pinfunction "3_3") (pintype "passive"))
      (node (ref "R28") (pin "2") (pinfunction "2_2") (pintype "passive"))
      (node (ref "U3") (pin "4") (pinfunction "OUT_4") (pintype "passive"))
      (node (ref "U3") (pin "5") (pinfunction "SENSE_5") (pintype "passive"))
    )
    (net (code "2") (name "+5V") (class "Default")
      (node (ref "C12") (pin "2") (pinfunction "2_2") (pintype "passive"))
      (node (ref "C14") (pin "2") (pinfunction "2_2") (pintype "passive"))
      (node (ref "C2") (pin "1") (pinfunction "1_1") (pintype "passive"))
      (node (ref "C6") (pin "2") (pinfunction "2_2") (pintype "passive"))
      (node (ref "J1") (pin "5") (pinfunction "5_5") (pintype "passive"))
      (node (ref "J8") (pin "1") (pinfunction "1_1") (pintype "passive"))
      (node (ref "JP4") (pin "1") (pinfunction "1_1") (pintype "passive"))
      (node (ref "L1") (pin "2") (pinfunction "2_2") (pintype "passive"))
      (node (ref "R27") (pin "1") (pinfunction "1_1") (pintype "passive"))
      (node (ref "U2") (pin "31") (pinfunction "UVCC_31") (pintype "passive"))
      (node (ref "U3") (pin "1") (pinfunction "~{SHDN}_1") (pintype "passive"))
      (node (ref "U3") (pin "2") (pinfunction "IN_2") (pintype "passive"))
    )
    (net (code "3") (name "+5V{slash}3V3") (class "Default")
      (node (ref "C15") (pin "2") (pinfunction "2_2") (pintype "passive"))
      (node (ref "C17") (pin "2") (pinfunction "2_2") (pintype "passive"))
      (node (ref "C26") (pin "2") (pinfunction "2_2") (pintype "passive"))
      (node (ref "C28") (pin "2") (pinfunction "2_2") (pintype "passive"))
      (node (ref "C29") (pin "2") (pinfunction "2_2") (pintype "passive"))
      (node (ref "C30") (pin "2") (pinfunction "2_2") (pintype "passive"))
      (node (ref "C34") (pin "2") (pinfunction "2_2") (pintype "passive"))
      (node (ref "C8") (pin "2") (pinfunction "2_2") (pintype "passive"))
      (node (ref "D5") (pin "1") (pinfunction "1_1") (pintype "passive"))
      (node (ref "D6") (pin "1") (pinfunction "1_1") (pintype "passive"))
      (node (ref "FB1") (pin "1") (pinfunction "1_1") (pintype "passive"))
      (node (ref "FB2") (pin "1") (pinfunction "1_1") (pintype "passive"))
      (node (ref "FB3") (pin "1") (pinfunction "1_1") (pintype "passive"))
      (node (ref "J1") (pin "2") (pinfunction "2_2") (pintype "passive"))
      (node (ref "J5") (pin "2") (pinfunction "2_2") (pintype "passive"))
      (node (ref "J6") (pin "2") (pinfunction "2_2") (pintype "passive"))
      (node (ref "JP4") (pin "2") (pinfunction "2_2") (pintype "passive"))
      (node (ref "R1") (pin "2") (pinfunction "2_2") (pintype "passive"))
      (node (ref "R14") (pin "2") (pinfunction "2_2") (pintype "passive"))
      (node (ref "R15") (pin "2") (pinfunction "2_2") (pintype "passive"))
      (node (ref "R17") (pin "2") (pinfunction "2_2") (pintype "passive"))
      (node (ref "R18") (pin "2") (pinfunction "2_2") (pintype "passive"))
      (node (ref "R19") (pin "2") (pinfunction "2_2") (pintype "passive"))
      (node (ref "R2") (pin "2") (pinfunction "2_2") (pintype "passive"))
      (node (ref "R20") (pin "2") (pinfunction "2_2") (pintype "passive"))
      (node (ref "R21") (pin "2") (pinfunction "2_2") (pintype "passive"))
      (node (ref "R27") (pin "2") (pinfunction "2_2") (pintype "passive"))
      (node (ref "R28") (pin "1") (pinfunction "1_1") (pintype "passive"))
      (node (ref "R3") (pin "2") (pinfunction "2_2") (pintype "passive"))
      (node (ref "R4") (pin "2") (pinfunction "2_2") (pintype "passive"))
      (node (ref "U4") (pin "5") (pinfunction "5_5") (pintype "passive"))
      (node (ref "U5") (pin "5") (pinfunction "5_5") (pintype "passive"))
      (node (ref "U6") (pin "5") (pinfunction "5_5") (pintype "passive"))
      (node (ref "U7") (pin "5") (pinfunction "5_5") (pintype "passive"))
    )
    (net (code "4") (name "+AREF") (class "Default")
      (node (ref "C21") (pin "2") (pinfunction "2_2") (pintype "passive"))
      (node (ref "C24") (pin "2") (pinfunction "2_2") (pintype "passive"))
      (node (ref "J4") (pin "8") (pinfunction "8_8") (pintype "passive"))
      (node (ref "U1") (pin "21") (pinfunction "AREF_21") (pintype "passive"))
    )
    (net (code "5") (name "/+3V3_16U2_UCAP") (class "Default")
      (node (ref "C7") (pin "2") (pinfunction "2_2") (pintype "passive"))
      (node (ref "R26") (pin "1") (pinfunction "1_1") (pintype "passive"))
      (node (ref "U2") (pin "27") (pinfunction "UCAP_27") (pintype "passive"))
    )
    (net (code "6") (name "/+5V_USB") (class "Default")
      (node (ref "C1") (pin "1") (pinfunction "1_1") (pintype "passive"))
      (node (ref "J7") (pin "1") (pinfunction "1_1") (pintype "passive"))
      (node (ref "L1") (pin "1") (pinfunction "1_1") (pintype "passive"))
    )
    (net (code "7") (name "/+5V{slash}3V3_16U2") (class "Default")
      (node (ref "C3") (pin "2") (pinfunction "2_2") (pintype "passive"))
      (node (ref "C4") (pin "2") (pinfunction "2_2") (pintype "passive"))
      (node (ref "C5") (pin "2") (pinfunction "2_2") (pintype "passive"))
      (node (ref "FB1") (pin "2") (pinfunction "2_2") (pintype "passive"))
      (node (ref "R26") (pin "2") (pinfunction "2_2") (pintype "passive"))
      (node (ref "U2") (pin "32") (pinfunction "AVCC_32") (pintype "passive"))
      (node (ref "U2") (pin "4") (pinfunction "VCC_4") (pintype "passive"))
    )
    (net (code "8") (name "/+5V{slash}3V3_328P_AVCC") (class "Default")
      (node (ref "C22") (pin "1") (pinfunction "1_1") (pintype "passive"))
      (node (ref "C23") (pin "2") (pinfunction "2_2") (pintype "passive"))
      (node (ref "FB3") (pin "2") (pinfunction "2_2") (pintype "passive"))
      (node (ref "U1") (pin "20") (pinfunction "AVCC_20") (pintype "passive"))
    )
    (net (code "9") (name "/+5V{slash}3V3_328P_VCC") (class "Default")
      (node (ref "C19") (pin "1") (pinfunction "1_1") (pintype "passive"))
      (node (ref "C20") (pin "2") (pinfunction "2_2") (pintype "passive"))
      (node (ref "FB2") (pin "2") (pinfunction "2_2") (pintype "passive"))
      (node (ref "U1") (pin "7") (pinfunction "VCC_7") (pintype "passive"))
    )
    (net (code "10") (name "/16U2PROG_328_RESETn") (class "Default")
      (node (ref "JP1") (pin "2") (pinfunction "2_2") (pintype "passive"))
      (node (ref "R1") (pin "1") (pinfunction "1_1") (pintype "passive"))
      (node (ref "U2") (pin "13") (pinfunction "/_~{HWB}_/_AIN6_/_T0_/_INT7)_PD7_13") (pintype "passive"))
    )
    (net (code "11") (name "/16U2_16MHZ_XTAL1") (class "Default")
      (node (ref "C10") (pin "1") (pinfunction "1_1") (pintype "passive"))
      (node (ref "R9") (pin "1") (pinfunction "1_1") (pintype "passive"))
      (node (ref "U2") (pin "1") (pinfunction "XTAL1_1") (pintype "passive"))
      (node (ref "Y2") (pin "1") (pinfunction "1_1") (pintype "passive"))
    )
    (net (code "12") (name "/16U2_16MHZ_XTAL2") (class "Default")
      (node (ref "C9") (pin "1") (pinfunction "1_1") (pintype "passive"))
      (node (ref "R9") (pin "2") (pinfunction "2_2") (pintype "passive"))
      (node (ref "U2") (pin "2") (pinfunction "(PC0)_XTAL2_2") (pintype "passive"))
      (node (ref "Y2") (pin "2") (pinfunction "2_2") (pintype "passive"))
    )
    (net (code "13") (name "/16U2_BUFF_RESETn") (class "Default")
      (node (ref "C31") (pin "2") (pinfunction "2_2") (pintype "passive"))
      (node (ref "R23") (pin "2") (pinfunction "2_2") (pintype "passive"))
      (node (ref "U5") (pin "1") (pinfunction "1_1") (pintype "input"))
      (node (ref "U5") (pin "2") (pinfunction "2_2") (pintype "input"))
    )
    (net (code "14") (name "/16U2_HDR_RESETn") (class "Default")
      (node (ref "J6") (pin "5") (pinfunction "5_5") (pintype "passive"))
      (node (ref "JP3") (pin "3") (pinfunction "3_3") (pintype "passive"))
    )
    (net (code "15") (name "/16U2_MISO") (class "Default")
      (node (ref "J6") (pin "1") (pinfunction "1_1") (pintype "passive"))
      (node (ref "U2") (pin "17") (pinfunction "PB3_(PDO_/_MISO_/_PCINT3)_17") (pintype "passive"))
    )
    (net (code "16") (name "/16U2_MOSI") (class "Default")
      (node (ref "J6") (pin "4") (pinfunction "4_4") (pintype "passive"))
      (node (ref "U2") (pin "16") (pinfunction "(PDI_/_MOSI_/_PCINT2)_PB2_16") (pintype "passive"))
    )
    (net (code "17") (name "/16U2_PB4") (class "Default")
      (node (ref "JP2") (pin "1") (pinfunction "1_1") (pintype "passive"))
      (node (ref "JP3") (pin "2") (pinfunction "2_2") (pintype "passive"))
      (node (ref "U2") (pin "18") (pinfunction "PB4_(T1_/_PCINT4)_18") (pintype "passive"))
    )
    (net (code "18") (name "/16U2_PB5") (class "Default")
      (node (ref "JP2") (pin "3") (pinfunction "3_3") (pintype "passive"))
      (node (ref "U2") (pin "19") (pinfunction "PB5_(PCINT5)_19") (pintype "passive"))
    )
    (net (code "19") (name "/16U2_PB6") (class "Default")
      (node (ref "JP2") (pin "2") (pinfunction "2_2") (pintype "passive"))
      (node (ref "U2") (pin "20") (pinfunction "PB6_(PCINT6)_20") (pintype "passive"))
    )
    (net (code "20") (name "/16U2_PB7") (class "Default")
      (node (ref "JP2") (pin "4") (pinfunction "4_4") (pintype "passive"))
      (node (ref "U2") (pin "21") (pinfunction "PB7_(PCINT7_/_OC.0A_/_OC.1C)_21") (pintype "passive"))
    )
    (net (code "21") (name "/16U2_RESETn") (class "Default")
      (node (ref "JP3") (pin "4") (pinfunction "4_4") (pintype "passive"))
      (node (ref "R4") (pin "1") (pinfunction "1_1") (pintype "passive"))
      (node (ref "U2") (pin "24") (pinfunction "~{RESET}_(PC1_/_dW)_24") (pintype "passive"))
      (node (ref "U5") (pin "4") (pinfunction "4_4") (pintype "output"))
    )
    (net (code "22") (name "/16U2_RXD") (class "Default")
      (node (ref "R11") (pin "1") (pinfunction "1_1") (pintype "passive"))
      (node (ref "U2") (pin "8") (pinfunction "(RXD1_/_AIN1_/_INT2)_PD2_8") (pintype "passive"))
    )
    (net (code "23") (name "/16U2_RX_LED") (class "Default")
      (node (ref "D4") (pin "1") (pinfunction "1_1") (pintype "passive"))
      (node (ref "U2") (pin "10") (pinfunction "(INT5/_AIN3)_PD4_10") (pintype "passive"))
    )
    (net (code "24") (name "/16U2_SCLK") (class "Default")
      (node (ref "J6") (pin "3") (pinfunction "3_3") (pintype "passive"))
      (node (ref "R5") (pin "2") (pinfunction "2_2") (pintype "passive"))
    )
    (net (code "25") (name "/16U2_SCLK_R") (class "Default")
      (node (ref "R5") (pin "1") (pinfunction "1_1") (pintype "passive"))
      (node (ref "U2") (pin "15") (pinfunction "(SCLK_/_PCINT1)_PB1_15") (pintype "passive"))
    )
    (net (code "26") (name "/16U2_TXD") (class "Default")
      (node (ref "R10") (pin "1") (pinfunction "1_1") (pintype "passive"))
      (node (ref "U2") (pin "9") (pinfunction "(TXD1_/_INT3)_PD3_9") (pintype "passive"))
    )
    (net (code "27") (name "/16U2_TX_LED") (class "Default")
      (node (ref "D3") (pin "1") (pinfunction "1_1") (pintype "passive"))
      (node (ref "U2") (pin "11") (pinfunction "(XCK_AIN4_/_PCINT12)_PD5_11") (pintype "passive"))
    )
    (net (code "28") (name "/328P_16MHZ_XTAL1") (class "Default")
      (node (ref "C27") (pin "1") (pinfunction "1_1") (pintype "passive"))
      (node (ref "R16") (pin "1") (pinfunction "1_1") (pintype "passive"))
      (node (ref "U1") (pin "9") (pinfunction "PB6_(PCINT6/XTAL1/TOSC1)_9") (pintype "passive"))
      (node (ref "Y1") (pin "1") (pinfunction "1_1") (pintype "passive"))
    )
    (net (code "29") (name "/328P_16MHZ_XTAL2") (class "Default")
      (node (ref "C25") (pin "1") (pinfunction "1_1") (pintype "passive"))
      (node (ref "R16") (pin "2") (pinfunction "2_2") (pintype "passive"))
      (node (ref "U1") (pin "10") (pinfunction "PB7_(PCINT7/XTAL2/TOSC2)_10") (pintype "passive"))
      (node (ref "Y1") (pin "2") (pinfunction "2_2") (pintype "passive"))
    )
    (net (code "30") (name "/328P_AUTORESETn") (class "Default")
      (node (ref "C11") (pin "1") (pinfunction "1_1") (pintype "passive"))
      (node (ref "R18") (pin "1") (pinfunction "1_1") (pintype "passive"))
      (node (ref "U6") (pin "1") (pinfunction "1_1") (pintype "input"))
    )
    (net (code "31") (name "/328P_BUFF_RESETn") (class "Default")
      (node (ref "C32") (pin "2") (pinfunction "2_2") (pintype "passive"))
      (node (ref "R24") (pin "2") (pinfunction "2_2") (pintype "passive"))
      (node (ref "U6") (pin "2") (pinfunction "2_2") (pintype "input"))
    )
    (net (code "32") (name "/328P_RESETn") (class "Default")
      (node (ref "J1") (pin "3") (pinfunction "3_3") (pintype "passive"))
      (node (ref "J5") (pin "5") (pinfunction "5_5") (pintype "passive"))
      (node (ref "JP3") (pin "1") (pinfunction "1_1") (pintype "passive"))
      (node (ref "R14") (pin "1") (pinfunction "1_1") (pintype "passive"))
      (node (ref "U1") (pin "1") (pinfunction "PC6_(PCINT14/~{RESET})_1") (pintype "passive"))
      (node (ref "U6") (pin "4") (pinfunction "4_4") (pintype "output"))
    )
    (net (code "33") (name "/AD0") (class "Default")
      (node (ref "J2") (pin "1") (pinfunction "1_1") (pintype "passive"))
      (node (ref "U1") (pin "23") (pinfunction "(ADC0/PCINT8)_PC0_23") (pintype "passive"))
    )
    (net (code "34") (name "/AD1") (class "Default")
      (node (ref "J2") (pin "2") (pinfunction "2_2") (pintype "passive"))
      (node (ref "U1") (pin "24") (pinfunction "(ADC1/PCINT9)_PC1_24") (pintype "passive"))
    )
    (net (code "35") (name "/AD2") (class "Default")
      (node (ref "J2") (pin "3") (pinfunction "3_3") (pintype "passive"))
      (node (ref "U1") (pin "25") (pinfunction "(ADC2/PCINT10)_PC2_25") (pintype "passive"))
    )
    (net (code "36") (name "/AD3") (class "Default")
      (node (ref "J2") (pin "4") (pinfunction "4_4") (pintype "passive"))
      (node (ref "U1") (pin "26") (pinfunction "(ADC3/PCINT11)_PC3_26") (pintype "passive"))
    )
    (net (code "37") (name "/AD4{slash}ADA") (class "Default")
      (node (ref "J2") (pin "5") (pinfunction "5_5") (pintype "passive"))
      (node (ref "J4") (pin "9") (pinfunction "9_9") (pintype "passive"))
      (node (ref "U1") (pin "27") (pinfunction "(ADC4/SDA/PCINT12)_PC4_27") (pintype "passive"))
    )
    (net (code "38") (name "/AD5{slash}SCL") (class "Default")
      (node (ref "J2") (pin "6") (pinfunction "6_6") (pintype "passive"))
      (node (ref "J4") (pin "10") (pinfunction "10_10") (pintype "passive"))
      (node (ref "U1") (pin "28") (pinfunction "(ADC5/SCL/PCINT13)_PC5_28") (pintype "passive"))
    )
    (net (code "39") (name "/BUTTON_RESETn") (class "Default")
      (node (ref "D6") (pin "2") (pinfunction "2_2") (pintype "passive"))
      (node (ref "R20") (pin "1") (pinfunction "1_1") (pintype "passive"))
      (node (ref "R24") (pin "1") (pinfunction "1_1") (pintype "passive"))
      (node (ref "SW1") (pin "1") (pinfunction "1_1") (pintype "passive"))
      (node (ref "SW1") (pin "2") (pinfunction "2_2") (pintype "passive"))
    )
    (net (code "40") (name "/CON_USB_N") (class "Default")
      (node (ref "J7") (pin "2") (pinfunction "2_2") (pintype "passive"))
      (node (ref "R6") (pin "1") (pinfunction "1_1") (pintype "passive"))
      (node (ref "Z1") (pin "2") (pinfunction "2_2") (pintype "passive"))
    )
    (net (code "41") (name "/CON_USB_P") (class "Default")
      (node (ref "J7") (pin "3") (pinfunction "3_3") (pintype "passive"))
      (node (ref "R7") (pin "1") (pinfunction "1_1") (pintype "passive"))
      (node (ref "Z2") (pin "2") (pinfunction "2_2") (pintype "passive"))
    )
    (net (code "42") (name "/IO0") (class "Default")
      (node (ref "J3") (pin "1") (pinfunction "1_1") (pintype "passive"))
      (node (ref "R10") (pin "2") (pinfunction "2_2") (pintype "passive"))
      (node (ref "U1") (pin "2") (pinfunction "(PCINT16/RXD)_PD0_2") (pintype "passive"))
    )
    (net (code "43") (name "/IO1") (class "Default")
      (node (ref "J3") (pin "2") (pinfunction "2_2") (pintype "passive"))
      (node (ref "R11") (pin "2") (pinfunction "2_2") (pintype "passive"))
      (node (ref "U1") (pin "3") (pinfunction "(PCINT17/TXD)_PD1_3") (pintype "passive"))
    )
    (net (code "44") (name "/IO2") (class "Default")
      (node (ref "J3") (pin "3") (pinfunction "3_3") (pintype "passive"))
      (node (ref "U1") (pin "4") (pinfunction "(PCINT18/INT0)_PD2_4") (pintype "passive"))
    )
    (net (code "45") (name "/IO3") (class "Default")
      (node (ref "J3") (pin "4") (pinfunction "4_4") (pintype "passive"))
      (node (ref "U1") (pin "5") (pinfunction "(PCINT19/OC2B/INT1)_PD3_5") (pintype "passive"))
    )
    (net (code "46") (name "/IO4") (class "Default")
      (node (ref "J3") (pin "5") (pinfunction "5_5") (pintype "passive"))
      (node (ref "U1") (pin "6") (pinfunction "(PCINT20/XCK/T0)_PD4_6") (pintype "passive"))
    )
    (net (code "47") (name "/IO5") (class "Default")
      (node (ref "J3") (pin "6") (pinfunction "6_6") (pintype "passive"))
      (node (ref "U1") (pin "11") (pinfunction "(PCINT21/OC0B/T1)_PD5_11") (pintype "passive"))
    )
    (net (code "48") (name "/IO6") (class "Default")
      (node (ref "J3") (pin "7") (pinfunction "7_7") (pintype "passive"))
      (node (ref "U1") (pin "12") (pinfunction "(PCINT22/OC0A/AIN0)_PD6_12") (pintype "passive"))
    )
    (net (code "49") (name "/IO7") (class "Default")
      (node (ref "J3") (pin "8") (pinfunction "8_8") (pintype "passive"))
      (node (ref "U1") (pin "13") (pinfunction "(PCINT23/AIN1)_PD7_13") (pintype "passive"))
    )
    (net (code "50") (name "/IO8") (class "Default")
      (node (ref "J4") (pin "1") (pinfunction "1_1") (pintype "passive"))
      (node (ref "R22") (pin "2") (pinfunction "2_2") (pintype "passive"))
      (node (ref "U1") (pin "14") (pinfunction "(PCINT0/CLKO/ICP1)_PB0_14") (pintype "passive"))
    )
    (net (code "51") (name "/IO9") (class "Default")
      (node (ref "J4") (pin "2") (pinfunction "2_2") (pintype "passive"))
      (node (ref "U1") (pin "15") (pinfunction "(OC1A/PCINT1)_PB1_15") (pintype "passive"))
    )
    (net (code "52") (name "/MISO") (class "Default")
      (node (ref "J4") (pin "5") (pinfunction "5_5") (pintype "passive"))
      (node (ref "J5") (pin "1") (pinfunction "1_1") (pintype "passive"))
      (node (ref "U1") (pin "18") (pinfunction "(MISO/PCINT4)_PB4_18") (pintype "passive"))
    )
    (net (code "53") (name "/MOSI") (class "Default")
      (node (ref "J4") (pin "4") (pinfunction "4_4") (pintype "passive"))
      (node (ref "J5") (pin "4") (pinfunction "4_4") (pintype "passive"))
      (node (ref "U1") (pin "17") (pinfunction "(MOSI/OC2A/PCINT3)_PB3_17") (pintype "passive"))
    )
    (net (code "54") (name "/SCK") (class "Default")
      (node (ref "J4") (pin "6") (pinfunction "6_6") (pintype "passive"))
      (node (ref "J5") (pin "3") (pinfunction "3_3") (pintype "passive"))
      (node (ref "R13") (pin "2") (pinfunction "2_2") (pintype "passive"))
      (node (ref "U4") (pin "1") (pinfunction "1_1") (pintype "input"))
      (node (ref "U4") (pin "2") (pinfunction "2_2") (pintype "input"))
    )
    (net (code "55") (name "/SCK_R") (class "Default")
      (node (ref "R13") (pin "1") (pinfunction "1_1") (pintype "passive"))
      (node (ref "U1") (pin "19") (pinfunction "(SCK/PCINT5)_PB5_19") (pintype "passive"))
    )
    (net (code "56") (name "/SS") (class "Default")
      (node (ref "J4") (pin "3") (pinfunction "3_3") (pintype "passive"))
      (node (ref "U1") (pin "16") (pinfunction "_(~{SS}/OC1B/PCINT2)_PB2_16") (pintype "passive"))
    )
    (net (code "57") (name "/USB_N") (class "Default")
      (node (ref "R6") (pin "2") (pinfunction "2_2") (pintype "passive"))
      (node (ref "U2") (pin "30") (pinfunction "D-_30") (pintype "passive"))
    )
    (net (code "58") (name "/USB_P") (class "Default")
      (node (ref "R7") (pin "2") (pinfunction "2_2") (pintype "passive"))
      (node (ref "U2") (pin "29") (pinfunction "D+_29") (pintype "passive"))
    )
    (net (code "59") (name "/USER_BUTTON") (class "Default")
      (node (ref "R21") (pin "1") (pinfunction "1_1") (pintype "passive"))
      (node (ref "R25") (pin "1") (pinfunction "1_1") (pintype "passive"))
      (node (ref "SW2") (pin "1") (pinfunction "1_1") (pintype "passive"))
      (node (ref "SW2") (pin "2") (pinfunction "2_2") (pintype "passive"))
    )
    (net (code "60") (name "/USER_BUTTON_BUFF") (class "Default")
      (node (ref "C33") (pin "2") (pinfunction "2_2") (pintype "passive"))
      (node (ref "R25") (pin "2") (pinfunction "2_2") (pintype "passive"))
      (node (ref "U7") (pin "1") (pinfunction "1_1") (pintype "input"))
      (node (ref "U7") (pin "2") (pinfunction "2_2") (pintype "input"))
    )
    (net (code "61") (name "GND") (class "Default")
      (node (ref "C1") (pin "2") (pinfunction "2_2") (pintype "passive"))
      (node (ref "C10") (pin "2") (pinfunction "2_2") (pintype "passive"))
      (node (ref "C12") (pin "1") (pinfunction "1_1") (pintype "passive"))
      (node (ref "C13") (pin "1") (pinfunction "1_1") (pintype "passive"))
      (node (ref "C14") (pin "1") (pinfunction "1_1") (pintype "passive"))
      (node (ref "C15") (pin "1") (pinfunction "1_1") (pintype "passive"))
      (node (ref "C16") (pin "1") (pinfunction "1_1") (pintype "passive"))
      (node (ref "C17") (pin "1") (pinfunction "1_1") (pintype "passive"))
      (node (ref "C19") (pin "2") (pinfunction "2_2") (pintype "passive"))
      (node (ref "C2") (pin "2") (pinfunction "2_2") (pintype "passive"))
      (node (ref "C20") (pin "1") (pinfunction "1_1") (pintype "passive"))
      (node (ref "C21") (pin "1") (pinfunction "1_1") (pintype "passive"))
      (node (ref "C22") (pin "2") (pinfunction "2_2") (pintype "passive"))
      (node (ref "C23") (pin "1") (pinfunction "1_1") (pintype "passive"))
      (node (ref "C24") (pin "1") (pinfunction "1_1") (pintype "passive"))
      (node (ref "C25") (pin "2") (pinfunction "2_2") (pintype "passive"))
      (node (ref "C26") (pin "1") (pinfunction "1_1") (pintype "passive"))
      (node (ref "C27") (pin "2") (pinfunction "2_2") (pintype "passive"))
      (node (ref "C28") (pin "1") (pinfunction "1_1") (pintype "passive"))
      (node (ref "C29") (pin "1") (pinfunction "1_1") (pintype "passive"))
      (node (ref "C3") (pin "1") (pinfunction "1_1") (pintype "passive"))
      (node (ref "C30") (pin "1") (pinfunction "1_1") (pintype "passive"))
      (node (ref "C31") (pin "1") (pinfunction "1_1") (pintype "passive"))
      (node (ref "C32") (pin "1") (pinfunction "1_1") (pintype "passive"))
      (node (ref "C33") (pin "1") (pinfunction "1_1") (pintype "passive"))
      (node (ref "C34") (pin "1") (pinfunction "1_1") (pintype "passive"))
      (node (ref "C4") (pin "1") (pinfunction "1_1") (pintype "passive"))
      (node (ref "C5") (pin "1") (pinfunction "1_1") (pintype "passive"))
      (node (ref "C6") (pin "1") (pinfunction "1_1") (pintype "passive"))
      (node (ref "C7") (pin "1") (pinfunction "1_1") (pintype "passive"))
      (node (ref "C8") (pin "1") (pinfunction "1_1") (pintype "passive"))
      (node (ref "C9") (pin "2") (pinfunction "2_2") (pintype "passive"))
      (node (ref "D1") (pin "1") (pinfunction "1_1") (pintype "passive"))
      (node (ref "J1") (pin "6") (pinfunction "6_6") (pintype "passive"))
      (node (ref "J1") (pin "7") (pinfunction "7_7") (pintype "passive"))
      (node (ref "J4") (pin "7") (pinfunction "7_7") (pintype "passive"))
      (node (ref "J5") (pin "6") (pinfunction "6_6") (pintype "passive"))
      (node (ref "J6") (pin "6") (pinfunction "6_6") (pintype "passive"))
      (node (ref "J7") (pin "10") (pinfunction "10_10") (pintype "passive"))
      (node (ref "J7") (pin "11") (pinfunction "11_11") (pintype "passive"))
      (node (ref "J7") (pin "5") (pinfunction "5_5") (pintype "passive"))
      (node (ref "J7") (pin "6") (pinfunction "6_6") (pintype "passive"))
      (node (ref "J7") (pin "7") (pinfunction "7_7") (pintype "passive"))
      (node (ref "J7") (pin "8") (pinfunction "8_8") (pintype "passive"))
      (node (ref "J7") (pin "9") (pinfunction "9_9") (pintype "passive"))
      (node (ref "J9") (pin "1") (pinfunction "1_1") (pintype "passive"))
      (node (ref "MH1") (pin "1") (pinfunction "1_1") (pintype "passive"))
      (node (ref "MH2") (pin "1") (pinfunction "1_1") (pintype "passive"))
      (node (ref "MH3") (pin "1") (pinfunction "1_1") (pintype "passive"))
      (node (ref "R12") (pin "1") (pinfunction "1_1") (pintype "passive"))
      (node (ref "R8") (pin "2") (pinfunction "2_2") (pintype "passive"))
      (node (ref "SW1") (pin "3") (pinfunction "3_3") (pintype "passive"))
      (node (ref "SW1") (pin "4") (pinfunction "4_4") (pintype "passive"))
      (node (ref "SW2") (pin "3") (pinfunction "3_3") (pintype "passive"))
      (node (ref "SW2") (pin "4") (pinfunction "4_4") (pintype "passive"))
      (node (ref "U1") (pin "22") (pinfunction "GND_2_22") (pintype "passive"))
      (node (ref "U1") (pin "8") (pinfunction "GND_1_8") (pintype "passive"))
      (node (ref "U2") (pin "28") (pinfunction "UGND_28") (pintype "passive"))
      (node (ref "U2") (pin "3") (pinfunction "GND_3") (pintype "passive"))
      (node (ref "U3") (pin "3") (pinfunction "GND_3") (pintype "passive"))
      (node (ref "U3") (pin "6") (pinfunction "EPAD_6") (pintype "passive"))
      (node (ref "U4") (pin "3") (pinfunction "3_3") (pintype "passive"))
      (node (ref "U5") (pin "3") (pinfunction "3_3") (pintype "passive"))
      (node (ref "U6") (pin "3") (pinfunction "3_3") (pintype "passive"))
      (node (ref "U7") (pin "3") (pinfunction "3_3") (pintype "passive"))
      (node (ref "Z1") (pin "1") (pinfunction "1_1") (pintype "passive"))
      (node (ref "Z2") (pin "1") (pinfunction "1_1") (pintype "passive"))
    )
    (net (code "62") (name "Net-(C11-Pad2)") (class "Default")
      (node (ref "C11") (pin "2") (pinfunction "2_2") (pintype "passive"))
      (node (ref "JP1") (pin "1") (pinfunction "1_1") (pintype "passive"))
    )
    (net (code "63") (name "Net-(D1-Pad2)") (class "Default")
      (node (ref "D1") (pin "2") (pinfunction "2_2") (pintype "passive"))
      (node (ref "R17") (pin "1") (pinfunction "1_1") (pintype "passive"))
    )
    (net (code "64") (name "Net-(D2-Pad1)") (class "Default")
      (node (ref "D2") (pin "1") (pinfunction "1_1") (pintype "passive"))
      (node (ref "U4") (pin "4") (pinfunction "4_4") (pintype "output"))
    )
    (net (code "65") (name "Net-(D2-Pad2)") (class "Default")
      (node (ref "D2") (pin "2") (pinfunction "2_2") (pintype "passive"))
      (node (ref "R15") (pin "1") (pinfunction "1_1") (pintype "passive"))
    )
    (net (code "66") (name "Net-(D3-Pad2)") (class "Default")
      (node (ref "D3") (pin "2") (pinfunction "2_2") (pintype "passive"))
      (node (ref "R2") (pin "1") (pinfunction "1_1") (pintype "passive"))
    )
    (net (code "67") (name "Net-(D4-Pad2)") (class "Default")
      (node (ref "D4") (pin "2") (pinfunction "2_2") (pintype "passive"))
      (node (ref "R3") (pin "1") (pinfunction "1_1") (pintype "passive"))
    )
    (net (code "68") (name "Net-(D5-Pad2)") (class "Default")
      (node (ref "D5") (pin "2") (pinfunction "2_2") (pintype "passive"))
      (node (ref "R19") (pin "1") (pinfunction "1_1") (pintype "passive"))
      (node (ref "R23") (pin "1") (pinfunction "1_1") (pintype "passive"))
    )
    (net (code "69") (name "Net-(J7-Pad4)") (class "Default")
      (node (ref "J7") (pin "4") (pinfunction "4_4") (pintype "passive"))
      (node (ref "R8") (pin "1") (pinfunction "1_1") (pintype "passive"))
    )
    (net (code "70") (name "Net-(JP1-Pad3)") (class "Default")
      (node (ref "JP1") (pin "3") (pinfunction "3_3") (pintype "passive"))
      (node (ref "R12") (pin "2") (pinfunction "2_2") (pintype "passive"))
    )
    (net (code "71") (name "Net-(R22-Pad1)") (class "Default")
      (node (ref "R22") (pin "1") (pinfunction "1_1") (pintype "passive"))
      (node (ref "U7") (pin "4") (pinfunction "4_4") (pintype "output"))
    )
    (net (code "72") (name "unconnected-(J1-Pad1)") (class "Default")
      (node (ref "J1") (pin "1") (pinfunction "1_1") (pintype "passive+no_connect"))
    )
    (net (code "73") (name "unconnected-(J1-Pad8)") (class "Default")
      (node (ref "J1") (pin "8") (pinfunction "8_8") (pintype "passive+no_connect"))
    )
    (net (code "74") (name "unconnected-(MH4-Pad1)") (class "Default")
      (node (ref "MH4") (pin "1") (pinfunction "1_1") (pintype "passive+no_connect"))
    )
    (net (code "75") (name "unconnected-(U2-(AIN0_{slash}_INT1)_PD1-Pad7)") (class "Default")
      (node (ref "U2") (pin "7") (pinfunction "(AIN0_/_INT1)_PD1_7") (pintype "passive+no_connect"))
    )
    (net (code "76") (name "unconnected-(U2-(OC.0B_{slash}_INT0)_PD0-Pad6)") (class "Default")
      (node (ref "U2") (pin "6") (pinfunction "(OC.0B_/_INT0)_PD0_6") (pintype "passive+no_connect"))
    )
    (net (code "77") (name "unconnected-(U2-(PCINT11_{slash}AIN2_)_PC2-Pad5)") (class "Default")
      (node (ref "U2") (pin "5") (pinfunction "(PCINT11_/AIN2_)_PC2_5") (pintype "passive+no_connect"))
    )
    (net (code "78") (name "unconnected-(U2-(~{RTS}_{slash}_AIN5_{slash}_INT6)_PD6-Pad12)") (class "Default")
      (node (ref "U2") (pin "12") (pinfunction "(~{RTS}_/_AIN5_/_INT6)_PD6_12") (pintype "passive+no_connect"))
    )
    (net (code "79") (name "unconnected-(U2-(~{SS}_{slash}_PCINT0)_PB0-Pad14)") (class "Default")
      (node (ref "U2") (pin "14") (pinfunction "(~{SS}_/_PCINT0)_PB0_14") (pintype "passive+no_connect"))
    )
    (net (code "80") (name "unconnected-(U2-PC4_(PCINT10)-Pad26)") (class "Default")
      (node (ref "U2") (pin "26") (pinfunction "PC4_(PCINT10)_26") (pintype "passive+no_connect"))
    )
    (net (code "81") (name "unconnected-(U2-PC5_(_PCINT9{slash}_OC.1B)-Pad25)") (class "Default")
      (node (ref "U2") (pin "25") (pinfunction "PC5_(_PCINT9/_OC.1B)_25") (pintype "passive+no_connect"))
    )
    (net (code "82") (name "unconnected-(U2-PC6_(OC.1A_{slash}_PCINT8)-Pad23)") (class "Default")
      (node (ref "U2") (pin "23") (pinfunction "PC6_(OC.1A_/_PCINT8)_23") (pintype "passive+no_connect"))
    )
    (net (code "83") (name "unconnected-(U2-PC7_(INT4_{slash}_ICP1_{slash}_CLKO)-Pad22)") (class "Default")
      (node (ref "U2") (pin "22") (pinfunction "PC7_(INT4_/_ICP1_/_CLKO)_22") (pintype "passive+no_connect"))
    )
  )
)
